# ARUv1.net
KiCad netlist of a schematic drawn in EAGLE
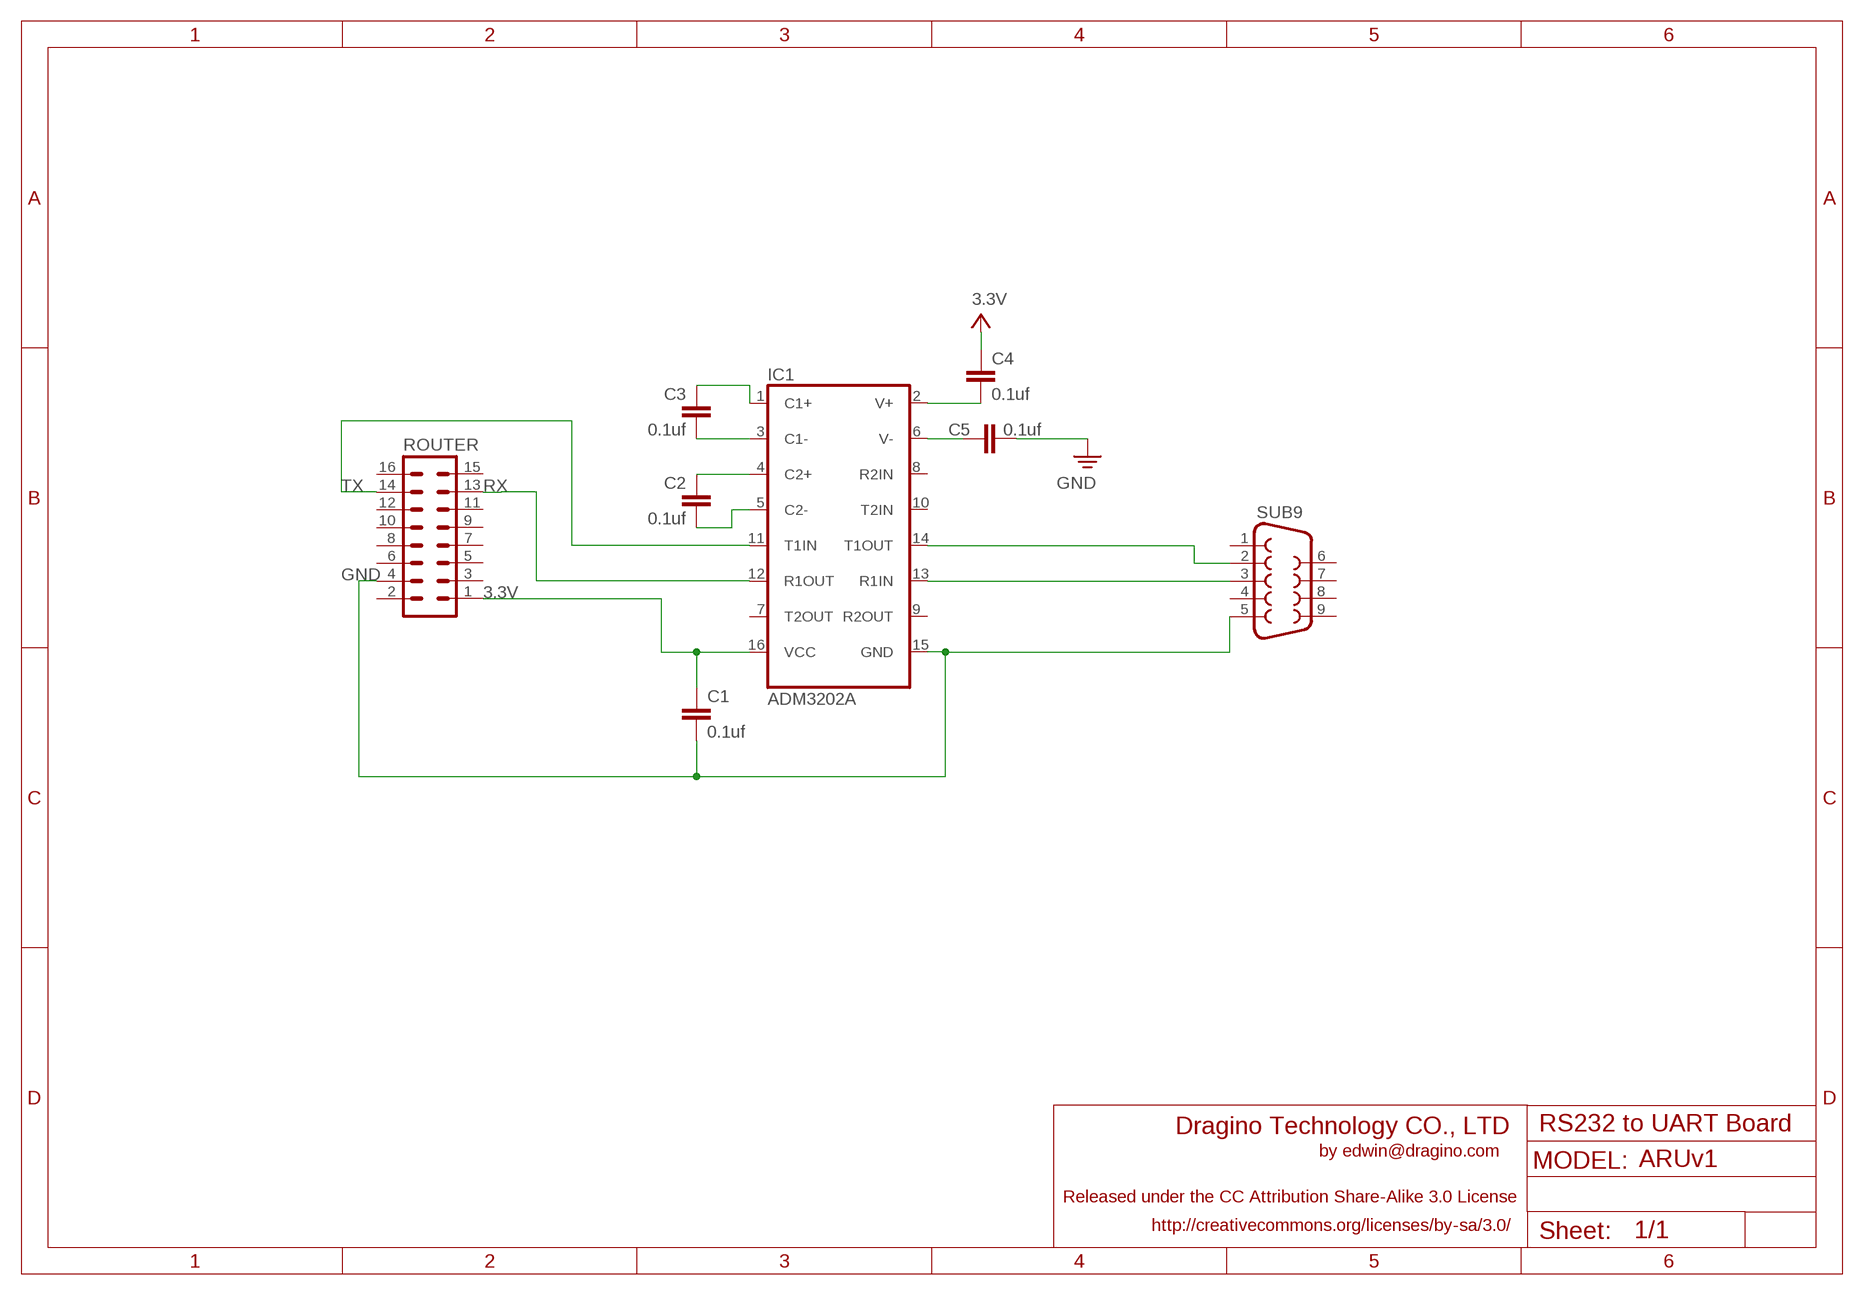
[diagram p0: schematic, sheet 1]

(export (version "E")
  (design (tool "Eeschema 10.0.6"))
  (components
    (comp (ref "C1")
      (value "0.1uf")
      (footprint "eagle-import:C0402")
      (libsource (lib "eagle-import") (part "C-EUC0402"))
    )
    (comp (ref "C2")
      (value "0.1uf")
      (footprint "eagle-import:C0402")
      (libsource (lib "eagle-import") (part "C-EUC0402"))
    )
    (comp (ref "C3")
      (value "0.1uf")
      (footprint "eagle-import:C0402")
      (libsource (lib "eagle-import") (part "C-EUC0402"))
    )
    (comp (ref "C4")
      (value "0.1uf")
      (footprint "eagle-import:C0402")
      (libsource (lib "eagle-import") (part "C-EUC0402"))
    )
    (comp (ref "C5")
      (value "0.1uf")
      (footprint "eagle-import:C0402")
      (libsource (lib "eagle-import") (part "C-EUC0402"))
    )
    (comp (ref "IC1")
      (value "ADM3202A")
      (footprint "eagle-import:TSSOP16")
      (fields (field (name "MF") "MAXIM") (field (name "MPN") "MAX3221CUE+"))
      (libsource (lib "eagle-import") (part "MAX3221UEC"))
    )
    (comp (ref "ROUTER")
      (value "MA08-2")
      (footprint "eagle-import:MA08-2")
      (libsource (lib "eagle-import") (part "MA08-2"))
    )
    (comp (ref "SUB9")
      (value "F09HP")
      (footprint "eagle-import:F09HP")
      (libsource (lib "eagle-import") (part "F09HP"))
    )
  )
  (nets
    (net (code "1") (name "/RX") (class "Default")
      (node (ref "IC1") (pin "12") (pinfunction "R1OUT_12") (pintype "output"))
      (node (ref "ROUTER") (pin "13") (pinfunction "13_13") (pintype "passive"))
    )
    (net (code "2") (name "/TX") (class "Default")
      (node (ref "IC1") (pin "11") (pinfunction "T1IN_11") (pintype "input"))
      (node (ref "ROUTER") (pin "14") (pinfunction "14_14") (pintype "passive"))
    )
    (net (code "3") (name "3.3V") (class "Default")
      (node (ref "C1") (pin "1") (pinfunction "1_1") (pintype "passive"))
      (node (ref "C4") (pin "1") (pinfunction "1_1") (pintype "passive"))
      (node (ref "IC1") (pin "16") (pinfunction "VCC_16") (pintype "bidirectional"))
      (node (ref "ROUTER") (pin "1") (pinfunction "1_1") (pintype "passive"))
    )
    (net (code "4") (name "GND") (class "Default")
      (node (ref "C1") (pin "2") (pinfunction "2_2") (pintype "passive"))
      (node (ref "C5") (pin "1") (pinfunction "1_1") (pintype "passive"))
      (node (ref "IC1") (pin "15") (pinfunction "GND_15") (pintype "bidirectional"))
      (node (ref "ROUTER") (pin "4") (pinfunction "4_4") (pintype "passive"))
      (node (ref "SUB9") (pin "5") (pinfunction "5_5") (pintype "passive"))
    )
    (net (code "5") (name "Net-(IC1-C1+)") (class "Default")
      (node (ref "C3") (pin "1") (pinfunction "1_1") (pintype "passive"))
      (node (ref "IC1") (pin "1") (pinfunction "C1+_1") (pintype "passive"))
    )
    (net (code "6") (name "Net-(IC1-C1-)") (class "Default")
      (node (ref "C3") (pin "2") (pinfunction "2_2") (pintype "passive"))
      (node (ref "IC1") (pin "3") (pinfunction "C1-_3") (pintype "passive"))
    )
    (net (code "7") (name "Net-(IC1-C2+)") (class "Default")
      (node (ref "C2") (pin "2") (pinfunction "2_2") (pintype "passive"))
      (node (ref "IC1") (pin "4") (pinfunction "C2+_4") (pintype "passive"))
    )
    (net (code "8") (name "Net-(IC1-C2-)") (class "Default")
      (node (ref "C2") (pin "1") (pinfunction "1_1") (pintype "passive"))
      (node (ref "IC1") (pin "5") (pinfunction "C2-_5") (pintype "passive"))
    )
    (net (code "9") (name "Net-(IC1-R1IN)") (class "Default")
      (node (ref "IC1") (pin "13") (pinfunction "R1IN_13") (pintype "input"))
      (node (ref "SUB9") (pin "3") (pinfunction "3_3") (pintype "passive"))
    )
    (net (code "10") (name "Net-(IC1-T1OUT)") (class "Default")
      (node (ref "IC1") (pin "14") (pinfunction "T1OUT_14") (pintype "output"))
      (node (ref "SUB9") (pin "2") (pinfunction "2_2") (pintype "passive"))
    )
    (net (code "11") (name "Net-(IC1-V+)") (class "Default")
      (node (ref "C4") (pin "2") (pinfunction "2_2") (pintype "passive"))
      (node (ref "IC1") (pin "2") (pinfunction "V+_2") (pintype "passive"))
    )
    (net (code "12") (name "Net-(IC1-V-)") (class "Default")
      (node (ref "C5") (pin "2") (pinfunction "2_2") (pintype "passive"))
      (node (ref "IC1") (pin "6") (pinfunction "V-_6") (pintype "passive"))
    )
    (net (code "13") (name "unconnected-(IC1-R2IN-Pad8)") (class "Default")
      (node (ref "IC1") (pin "8") (pinfunction "R2IN_8") (pintype "input"))
    )
    (net (code "14") (name "unconnected-(IC1-R2OUT-Pad9)") (class "Default")
      (node (ref "IC1") (pin "9") (pinfunction "R2OUT_9") (pintype "input"))
    )
    (net (code "15") (name "unconnected-(IC1-T2IN-Pad10)") (class "Default")
      (node (ref "IC1") (pin "10") (pinfunction "T2IN_10") (pintype "input"))
    )
    (net (code "16") (name "unconnected-(IC1-T2OUT-Pad7)") (class "Default")
      (node (ref "IC1") (pin "7") (pinfunction "T2OUT_7") (pintype "input"))
    )
    (net (code "17") (name "unconnected-(ROUTER-Pad2)") (class "Default")
      (node (ref "ROUTER") (pin "2") (pinfunction "2_2") (pintype "passive"))
    )
    (net (code "18") (name "unconnected-(ROUTER-Pad3)") (class "Default")
      (node (ref "ROUTER") (pin "3") (pinfunction "3_3") (pintype "passive"))
    )
    (net (code "19") (name "unconnected-(ROUTER-Pad5)") (class "Default")
      (node (ref "ROUTER") (pin "5") (pinfunction "5_5") (pintype "passive"))
    )
    (net (code "20") (name "unconnected-(ROUTER-Pad6)") (class "Default")
      (node (ref "ROUTER") (pin "6") (pinfunction "6_6") (pintype "passive"))
    )
    (net (code "21") (name "unconnected-(ROUTER-Pad7)") (class "Default")
      (node (ref "ROUTER") (pin "7") (pinfunction "7_7") (pintype "passive"))
    )
    (net (code "22") (name "unconnected-(ROUTER-Pad8)") (class "Default")
      (node (ref "ROUTER") (pin "8") (pinfunction "8_8") (pintype "passive"))
    )
    (net (code "23") (name "unconnected-(ROUTER-Pad9)") (class "Default")
      (node (ref "ROUTER") (pin "9") (pinfunction "9_9") (pintype "passive"))
    )
    (net (code "24") (name "unconnected-(ROUTER-Pad10)") (class "Default")
      (node (ref "ROUTER") (pin "10") (pinfunction "10_10") (pintype "passive"))
    )
    (net (code "25") (name "unconnected-(ROUTER-Pad11)") (class "Default")
      (node (ref "ROUTER") (pin "11") (pinfunction "11_11") (pintype "passive"))
    )
    (net (code "26") (name "unconnected-(ROUTER-Pad12)") (class "Default")
      (node (ref "ROUTER") (pin "12") (pinfunction "12_12") (pintype "passive"))
    )
    (net (code "27") (name "unconnected-(ROUTER-Pad15)") (class "Default")
      (node (ref "ROUTER") (pin "15") (pinfunction "15_15") (pintype "passive"))
    )
    (net (code "28") (name "unconnected-(ROUTER-Pad16)") (class "Default")
      (node (ref "ROUTER") (pin "16") (pinfunction "16_16") (pintype "passive"))
    )
    (net (code "29") (name "unconnected-(SUB9-Pad1)") (class "Default")
      (node (ref "SUB9") (pin "1") (pinfunction "1_1") (pintype "passive"))
    )
    (net (code "30") (name "unconnected-(SUB9-Pad4)") (class "Default")
      (node (ref "SUB9") (pin "4") (pinfunction "4_4") (pintype "passive"))
    )
    (net (code "31") (name "unconnected-(SUB9-Pad6)") (class "Default")
      (node (ref "SUB9") (pin "6") (pinfunction "6_6") (pintype "passive"))
    )
    (net (code "32") (name "unconnected-(SUB9-Pad7)") (class "Default")
      (node (ref "SUB9") (pin "7") (pinfunction "7_7") (pintype "passive"))
    )
    (net (code "33") (name "unconnected-(SUB9-Pad8)") (class "Default")
      (node (ref "SUB9") (pin "8") (pinfunction "8_8") (pintype "passive"))
    )
    (net (code "34") (name "unconnected-(SUB9-Pad9)") (class "Default")
      (node (ref "SUB9") (pin "9") (pinfunction "9_9") (pintype "passive"))
    )
  )
)
